# Protection.net
KiCad netlist of a schematic drawn in Altium Designer
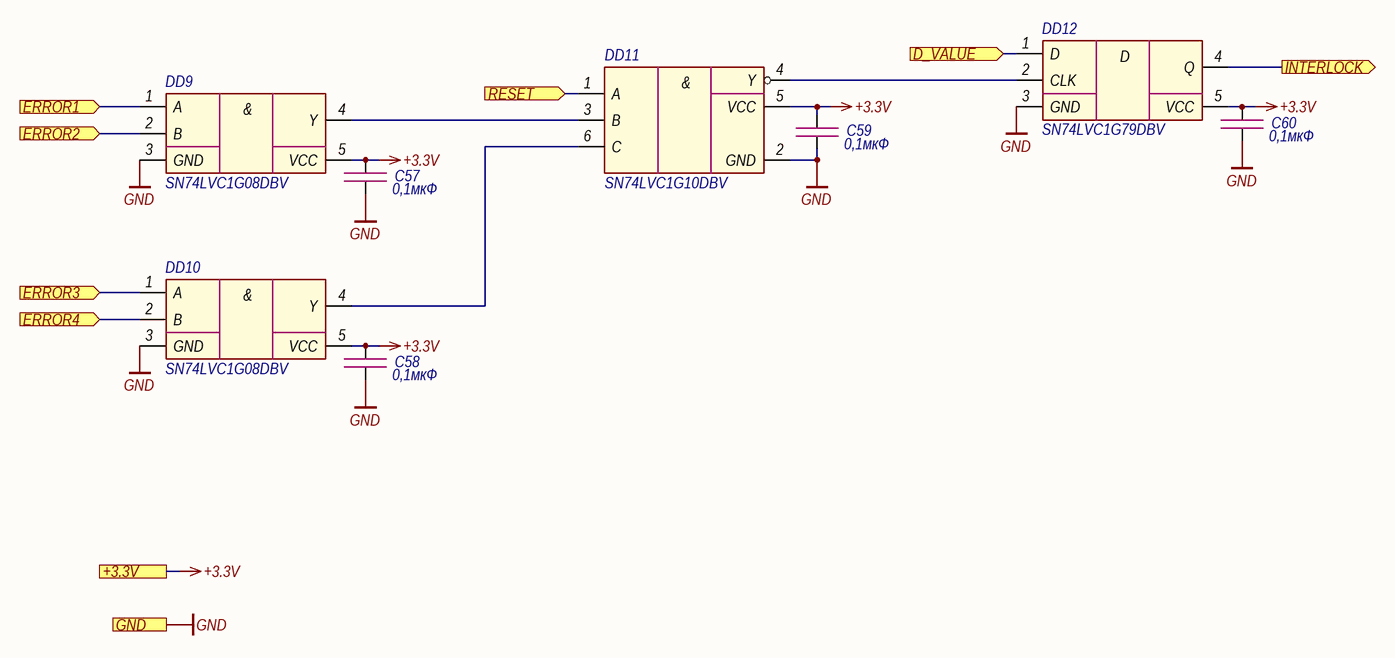
[diagram p0: Protection.SchDoc]

(export (version "E")
  (design (tool "Eeschema 10.0.6"))
  (components
    (comp (ref "C57")
      (value "0,1мкФ")
      (footprint "Pcb_library:CAP_0603")
      (fields (field (name "MANUFACTURER") "Murata"))
      (libsource (lib "Schem_library") (part "Capacitor"))
    )
    (comp (ref "C58")
      (value "0,1мкФ")
      (footprint "Pcb_library:CAP_0603")
      (fields (field (name "MANUFACTURER") "Murata"))
      (libsource (lib "Schem_library") (part "Capacitor"))
    )
    (comp (ref "C59")
      (value "0,1мкФ")
      (footprint "Pcb_library:CAP_0603")
      (fields (field (name "MANUFACTURER") "Murata"))
      (libsource (lib "Schem_library") (part "Capacitor"))
    )
    (comp (ref "C60")
      (value "0,1мкФ")
      (footprint "Pcb_library:CAP_0603")
      (fields (field (name "MANUFACTURER") "Murata"))
      (libsource (lib "Schem_library") (part "Capacitor"))
    )
    (comp (ref "DD9")
      (value "SN74LVC1G08DBV")
      (footprint "Pcb_library:SOT-23-5")
      (fields (field (name "MANUFACTURER") "Texas Instruments"))
      (libsource (lib "Schem_library") (part "SN74LVC1G08"))
    )
    (comp (ref "DD10")
      (value "SN74LVC1G08DBV")
      (footprint "Pcb_library:SOT-23-5")
      (fields (field (name "MANUFACTURER") "Texas Instruments"))
      (libsource (lib "Schem_library") (part "SN74LVC1G08"))
    )
    (comp (ref "DD11")
      (value "SN74LVC1G10DBV")
      (footprint "Pcb_library:SOT-23-6")
      (fields (field (name "MANUFACTURER") "Texas Instruments"))
      (libsource (lib "Schem_library") (part "SN74LVC1G10"))
    )
    (comp (ref "DD12")
      (value "SN74LVC1G79DBV")
      (footprint "Pcb_library:SOT-23-5")
      (fields (field (name "MANUFACTURER") "Texas Instruments"))
      (libsource (lib "Schem_library") (part "SN74LVC1G79"))
    )
  )
  (nets
    (net (code "1") (name "+3.3V") (class "Default")
      (node (ref "C57") (pin "1") (pinfunction "1_1") (pintype "passive"))
      (node (ref "C58") (pin "1") (pinfunction "1_1") (pintype "passive"))
      (node (ref "C59") (pin "1") (pinfunction "1_1") (pintype "passive"))
      (node (ref "C60") (pin "1") (pinfunction "1_1") (pintype "passive"))
      (node (ref "DD10") (pin "5") (pinfunction "VCC_5") (pintype "passive"))
      (node (ref "DD11") (pin "5") (pinfunction "VCC_5") (pintype "passive"))
      (node (ref "DD12") (pin "5") (pinfunction "VCC_5") (pintype "passive"))
      (node (ref "DD9") (pin "5") (pinfunction "VCC_5") (pintype "passive"))
    )
    (net (code "2") (name "/D_VALUE") (class "Default")
      (node (ref "DD12") (pin "1") (pinfunction "D_1") (pintype "passive"))
    )
    (net (code "3") (name "/ERROR1") (class "Default")
      (node (ref "DD9") (pin "1") (pinfunction "A_1") (pintype "passive"))
    )
    (net (code "4") (name "/ERROR2") (class "Default")
      (node (ref "DD9") (pin "2") (pinfunction "B_2") (pintype "passive"))
    )
    (net (code "5") (name "/ERROR3") (class "Default")
      (node (ref "DD10") (pin "1") (pinfunction "A_1") (pintype "passive"))
    )
    (net (code "6") (name "/ERROR4") (class "Default")
      (node (ref "DD10") (pin "2") (pinfunction "B_2") (pintype "passive"))
    )
    (net (code "7") (name "/INTERLOCK") (class "Default")
      (node (ref "DD12") (pin "4") (pinfunction "Q_4") (pintype "passive"))
    )
    (net (code "8") (name "/RESET") (class "Default")
      (node (ref "DD11") (pin "1") (pinfunction "A_1") (pintype "passive"))
    )
    (net (code "9") (name "GND") (class "Default")
      (node (ref "C57") (pin "2") (pinfunction "2_2") (pintype "passive"))
      (node (ref "C58") (pin "2") (pinfunction "2_2") (pintype "passive"))
      (node (ref "C59") (pin "2") (pinfunction "2_2") (pintype "passive"))
      (node (ref "C60") (pin "2") (pinfunction "2_2") (pintype "passive"))
      (node (ref "DD10") (pin "3") (pinfunction "GND_3") (pintype "passive"))
      (node (ref "DD11") (pin "2") (pinfunction "GND_2") (pintype "passive"))
      (node (ref "DD12") (pin "3") (pinfunction "GND_3") (pintype "passive"))
      (node (ref "DD9") (pin "3") (pinfunction "GND_3") (pintype "passive"))
    )
    (net (code "10") (name "Net-(DD10-Y)") (class "Default")
      (node (ref "DD10") (pin "4") (pinfunction "Y_4") (pintype "passive"))
      (node (ref "DD11") (pin "6") (pinfunction "C_6") (pintype "passive"))
    )
    (net (code "11") (name "Net-(DD11-B)") (class "Default")
      (node (ref "DD11") (pin "3") (pinfunction "B_3") (pintype "passive"))
      (node (ref "DD9") (pin "4") (pinfunction "Y_4") (pintype "passive"))
    )
    (net (code "12") (name "Net-(DD11-Y)") (class "Default")
      (node (ref "DD11") (pin "4") (pinfunction "Y_4") (pintype "passive"))
      (node (ref "DD12") (pin "2") (pinfunction "CLK_2") (pintype "passive"))
    )
  )
)
